# QEP.net
KiCad netlist of a schematic drawn in Altium Designer
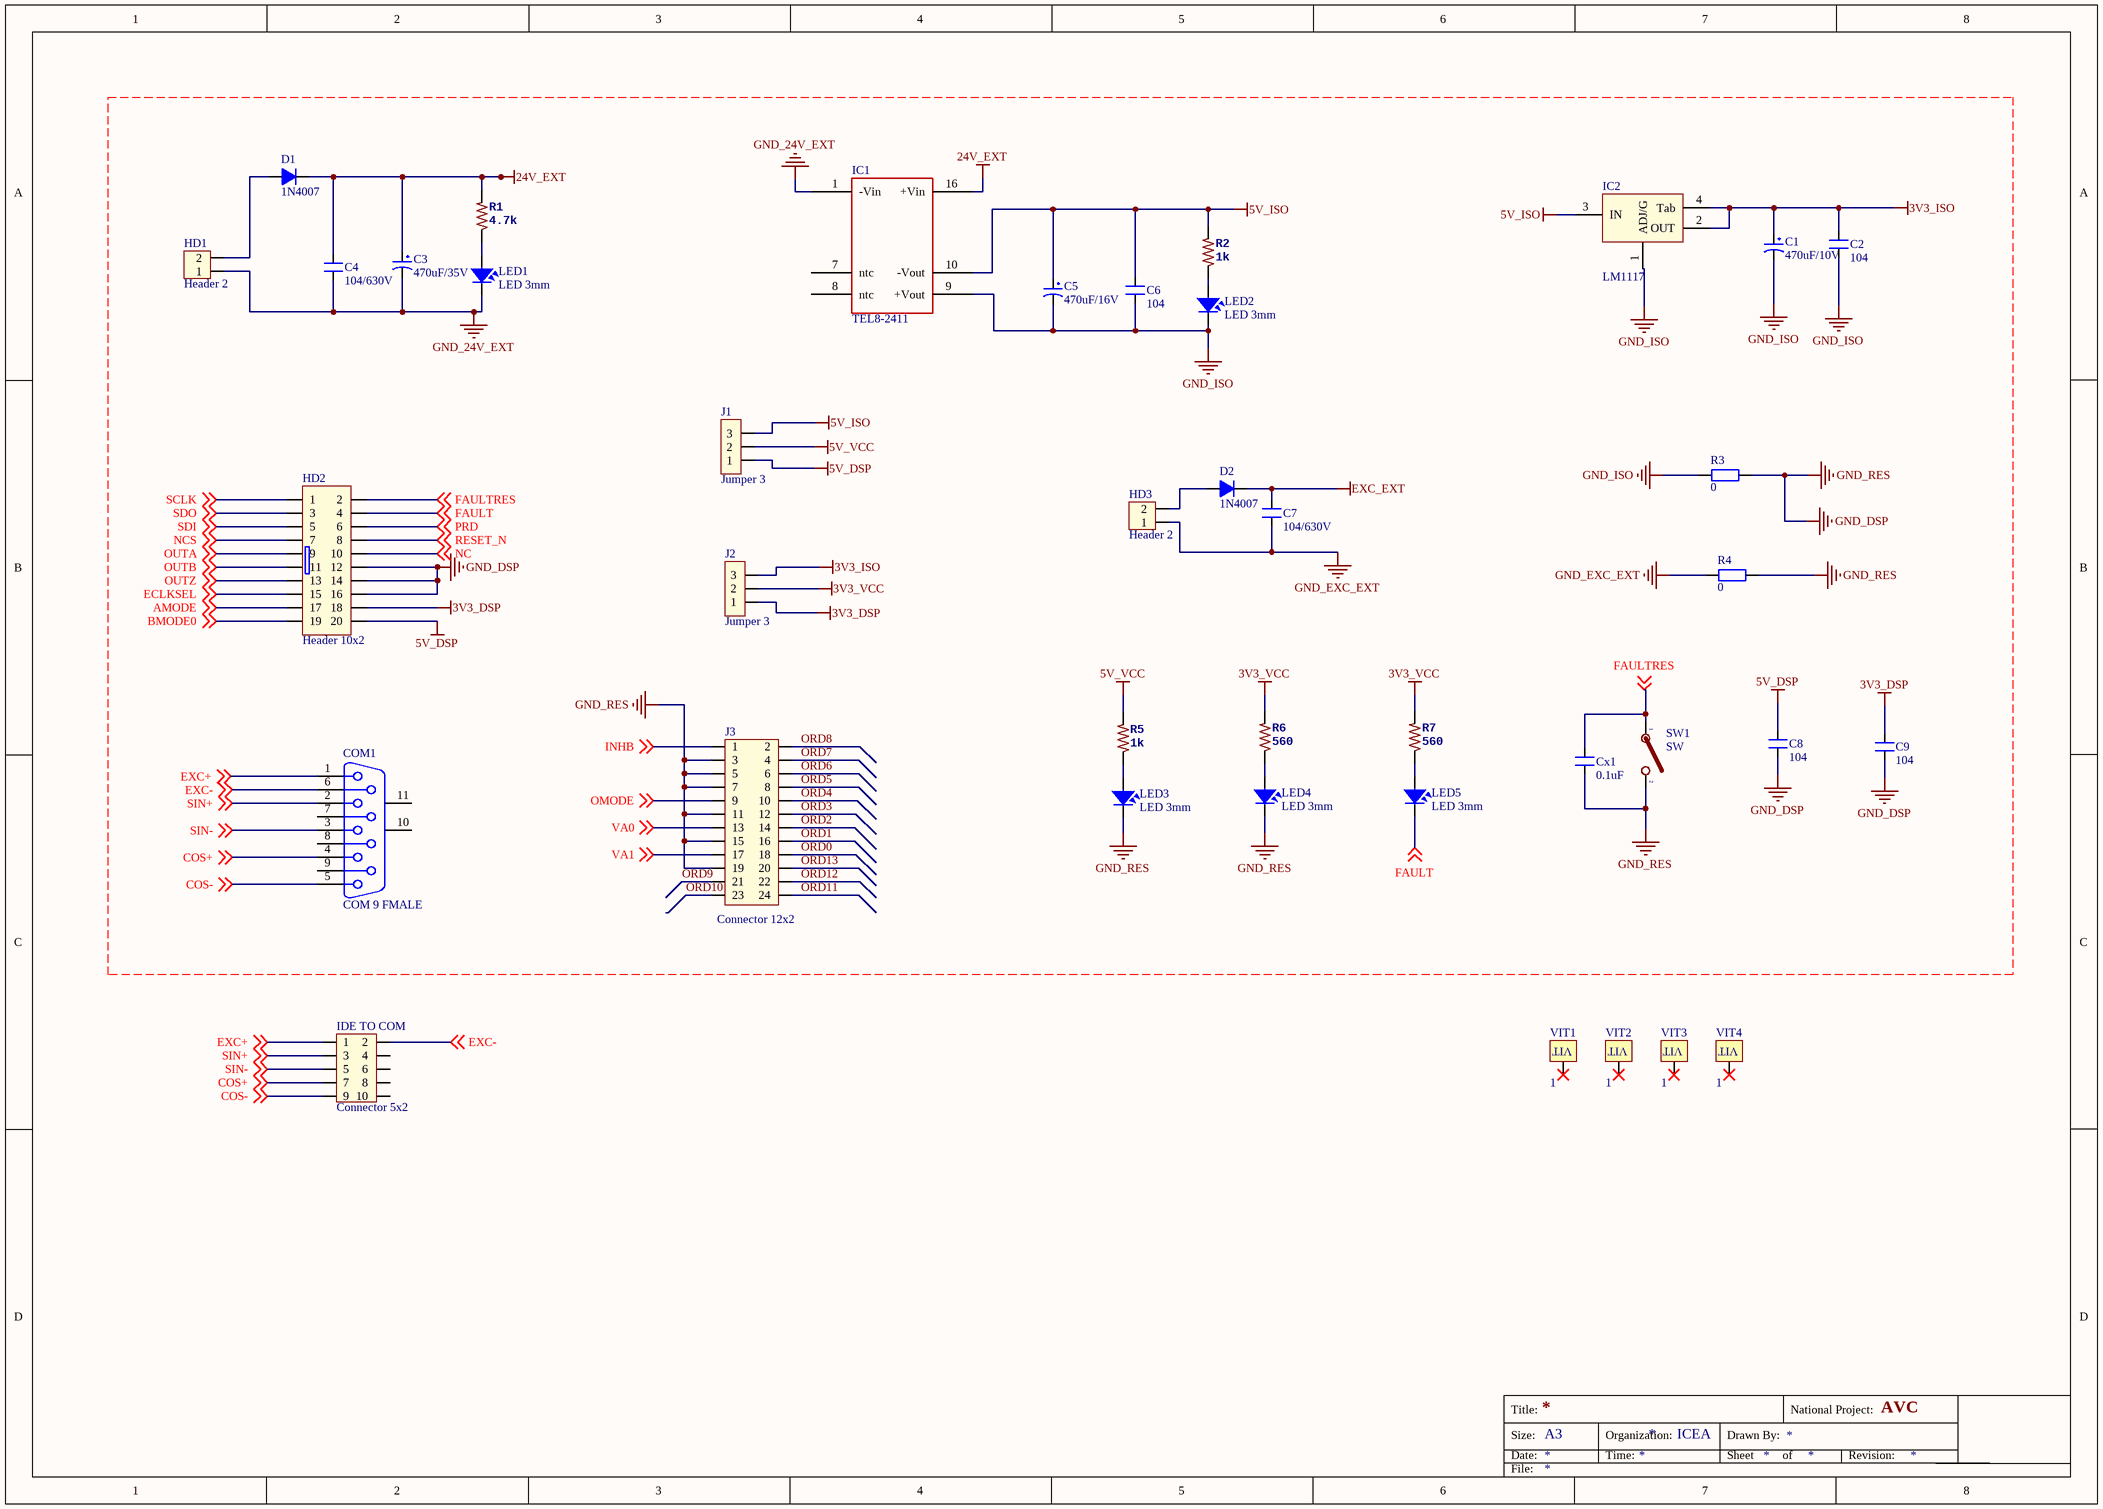
[diagram p0: QEP.SchDoc]

(export (version "E")
  (design (tool "Eeschema 10.0.6"))
  (components
    (comp (ref "C1")
      (value "470uF/10V")
      (footprint "CP 470uF/35V SMD 10x10mm")
      (description "Cap 100uF/35V - 470uF/16V")
      (libsource (lib "PELAB") (part "CP3"))
    )
    (comp (ref "C2")
      (value "104")
      (footprint "CN1.5")
      (description "Cap np 682pF => 104pF")
      (libsource (lib "PELAB") (part "CN1.5"))
    )
    (comp (ref "C3")
      (value "470uF/35V")
      (footprint "CP 470uF/35V SMD 10x10mm")
      (description "Cap 100uF/35V - 470uF/16V")
      (libsource (lib "PELAB") (part "CP3"))
    )
    (comp (ref "C4")
      (value "104/630V")
      (footprint "CN3")
      (description "Cap np W0.3")
      (fields (field (name "COPYRIGHT") "VanDungEvn"))
      (libsource (lib "PELAB") (part "CN3"))
    )
    (comp (ref "C5")
      (value "470uF/16V")
      (footprint "CP 470uF/35V SMD 10x10mm")
      (description "Cap 100uF/35V - 470uF/16V")
      (libsource (lib "PELAB") (part "CP3"))
    )
    (comp (ref "C6")
      (value "104")
      (footprint "CN1.5")
      (description "Cap np 682pF => 104pF")
      (libsource (lib "PELAB") (part "CN1.5"))
    )
    (comp (ref "C7")
      (value "104/630V")
      (footprint "CN3")
      (description "Cap np W0.3")
      (fields (field (name "COPYRIGHT") "VanDungEvn"))
      (libsource (lib "PELAB") (part "CN3"))
    )
    (comp (ref "C8")
      (value "104")
      (footprint "CN1.5")
      (description "Cap np 682pF => 104pF")
      (libsource (lib "PELAB") (part "CN1.5"))
    )
    (comp (ref "C9")
      (value "104")
      (footprint "CN1.5")
      (description "Cap np 682pF => 104pF")
      (libsource (lib "PELAB") (part "CN1.5"))
    )
    (comp (ref "COM1")
      (value "COM 9 FMALE")
      (footprint "DSB 9-F")
      (description "COM 9")
      (fields (field (name "PUBLISHER") "Altium Limited"))
      (libsource (lib "PELAB") (part "DSB9F"))
    )
    (comp (ref "Cx1")
      (value "0.1uF")
      (footprint "CN-SMD-0805")
      (libsource (lib "ImetAltiumLibrary") (part "CN"))
    )
    (comp (ref "D1")
      (value "1N4007")
      (footprint "DIO-SMD-106")
      (description "Diode 2A")
      (libsource (lib "PELAB") (part "D2A"))
    )
    (comp (ref "D2")
      (value "1N4007")
      (footprint "DIO-SMD-106")
      (description "Diode 2A")
      (libsource (lib "PELAB") (part "D2A"))
    )
    (comp (ref "HD1")
      (value "Header 2")
      (footprint "HED2T")
      (description "Header 2 (Green)")
      (libsource (lib "PELAB") (part "Hed2"))
    )
    (comp (ref "HD2") (value "Header 10x2") (footprint "IDE 20") (libsource (lib "PELAB") (part "HED10X2")))
    (comp (ref "HD3")
      (value "Header 2")
      (footprint "HED2T")
      (description "Header 2 (Green)")
      (libsource (lib "PELAB") (part "Hed2"))
    )
    (comp (ref "IC1")
      (value "TEL8-2411")
      (footprint "TEL8-2411")
      (libsource (lib "PELAB") (part "TEL8-2411"))
    )
    (comp (ref "IC2")
      (value "LM1117")
      (footprint "SOT223-4N")
      (description "3v3")
      (libsource (lib "PELAB") (part "LM1117"))
    )
    (comp (ref "IDE TO COM")
      (value "Connector 5x2")
      (footprint "IDE 10 duc")
      (libsource (lib "PELAB") (part "JP5x2"))
    )
    (comp (ref "J1") (value "Jumper 3") (footprint "JP3-CLOSED") (libsource (lib "PELAB") (part "JP3")))
    (comp (ref "J2") (value "Jumper 3") (footprint "JP3-CLOSED") (libsource (lib "PELAB") (part "JP3")))
    (comp (ref "J3") (value "Connector 12x2") (footprint "JP12X2") (libsource (lib "PELAB") (part "JP12x2")))
    (comp (ref "LED1")
      (value "LED 3mm")
      (footprint "LED-0805-Red")
      (description "LED Single colour Green and Red")
      (libsource (lib "PELAB") (part "LED 3mm"))
    )
    (comp (ref "LED2")
      (value "LED 3mm")
      (footprint "LED-0805-Red")
      (description "LED Single colour Green and Red")
      (libsource (lib "PELAB") (part "LED 3mm"))
    )
    (comp (ref "LED3")
      (value "LED 3mm")
      (footprint "LED-0805-Red")
      (description "LED Single colour Green and Red")
      (libsource (lib "PELAB") (part "LED 3mm"))
    )
    (comp (ref "LED4")
      (value "LED 3mm")
      (footprint "LED-0805-Red")
      (description "LED Single colour Green and Red")
      (libsource (lib "PELAB") (part "LED 3mm"))
    )
    (comp (ref "LED5")
      (value "LED 3mm")
      (footprint "LED-0805-Red")
      (description "LED Single colour Green and Red")
      (libsource (lib "PELAB") (part "LED 3mm"))
    )
    (comp (ref "R1")
      (value "4.7k")
      (footprint "SM-0805")
      (description "RESISTOR, American symbol")
      (libsource (lib "PELAB") (part "R-US_R0805"))
    )
    (comp (ref "R2")
      (value "1k")
      (footprint "RES-SMD-0805")
      (description "RESISTOR, American symbol")
      (libsource (lib "PELAB") (part "R-US_R0805"))
    )
    (comp (ref "R3")
      (value "0")
      (footprint "RES-SMD-0805")
      (description "Resistor 1/4W")
      (libsource (lib "PELAB") (part "R1/4W"))
    )
    (comp (ref "R4")
      (value "0")
      (footprint "RES-SMD-0805")
      (description "Resistor 1/4W")
      (libsource (lib "PELAB") (part "R1/4W"))
    )
    (comp (ref "R5")
      (value "1k")
      (footprint "RES-SMD-0805")
      (description "RESISTOR, American symbol")
      (libsource (lib "PELAB") (part "R-US_R0805"))
    )
    (comp (ref "R6")
      (value "560")
      (footprint "RES-SMD-0805")
      (description "RESISTOR, American symbol")
      (libsource (lib "PELAB") (part "R-US_R0805"))
    )
    (comp (ref "R7")
      (value "560")
      (footprint "RES-SMD-0805")
      (description "RESISTOR, American symbol")
      (libsource (lib "PELAB") (part "R-US_R0805"))
    )
    (comp (ref "SW1")
      (value "SW")
      (footprint "SW-SMD")
      (description "Switch button 2 pin")
      (libsource (lib "PELAB") (part "SW"))
    )
    (comp (ref "VIT1")
      (value "1")
      (footprint "VIT")
      (description "Oc Vit")
      (libsource (lib "PELAB") (part "VIT"))
    )
    (comp (ref "VIT2")
      (value "1")
      (footprint "VIT")
      (description "Oc Vit")
      (libsource (lib "PELAB") (part "VIT"))
    )
    (comp (ref "VIT3")
      (value "1")
      (footprint "VIT")
      (description "Oc Vit")
      (libsource (lib "PELAB") (part "VIT"))
    )
    (comp (ref "VIT4")
      (value "1")
      (footprint "VIT")
      (description "Oc Vit")
      (libsource (lib "PELAB") (part "VIT"))
    )
  )
  (nets
    (net (code "1") (name "/ORD0") (class "Default")
      (node (ref "J3") (pin "18") (pinfunction "18_18") (pintype "passive"))
    )
    (net (code "2") (name "/ORD1") (class "Default")
      (node (ref "J3") (pin "16") (pinfunction "16_16") (pintype "passive"))
    )
    (net (code "3") (name "/ORD2") (class "Default")
      (node (ref "J3") (pin "14") (pinfunction "14_14") (pintype "passive"))
    )
    (net (code "4") (name "/ORD3") (class "Default")
      (node (ref "J3") (pin "12") (pinfunction "12_12") (pintype "passive"))
    )
    (net (code "5") (name "/ORD4") (class "Default")
      (node (ref "J3") (pin "10") (pinfunction "10_10") (pintype "passive"))
    )
    (net (code "6") (name "/ORD5") (class "Default")
      (node (ref "J3") (pin "8") (pinfunction "8_8") (pintype "passive"))
    )
    (net (code "7") (name "/ORD6") (class "Default")
      (node (ref "J3") (pin "6") (pinfunction "6_6") (pintype "passive"))
    )
    (net (code "8") (name "/ORD7") (class "Default")
      (node (ref "J3") (pin "4") (pinfunction "4_4") (pintype "passive"))
    )
    (net (code "9") (name "/ORD8") (class "Default")
      (node (ref "J3") (pin "2") (pinfunction "2_2") (pintype "passive"))
    )
    (net (code "10") (name "/ORD9") (class "Default")
      (node (ref "J3") (pin "21") (pinfunction "21_21") (pintype "passive"))
    )
    (net (code "11") (name "/ORD10") (class "Default")
      (node (ref "J3") (pin "23") (pinfunction "23_23") (pintype "passive"))
    )
    (net (code "12") (name "/ORD11") (class "Default")
      (node (ref "J3") (pin "24") (pinfunction "24_24") (pintype "passive"))
    )
    (net (code "13") (name "/ORD12") (class "Default")
      (node (ref "J3") (pin "22") (pinfunction "22_22") (pintype "passive"))
    )
    (net (code "14") (name "/ORD13") (class "Default")
      (node (ref "J3") (pin "20") (pinfunction "20_20") (pintype "passive"))
    )
    (net (code "15") (name "3V3_DSP") (class "Default")
      (node (ref "C9") (pin "2") (pinfunction "2_2") (pintype "passive"))
      (node (ref "HD2") (pin "18") (pinfunction "18_18") (pintype "passive"))
      (node (ref "J2") (pin "1") (pinfunction "1_1") (pintype "passive"))
    )
    (net (code "16") (name "3V3_ISO") (class "Default")
      (node (ref "C1") (pin "1") (pinfunction "1_1") (pintype "passive"))
      (node (ref "C2") (pin "2") (pinfunction "2_2") (pintype "passive"))
      (node (ref "IC2") (pin "2") (pinfunction "OUT_2") (pintype "passive"))
      (node (ref "IC2") (pin "4") (pinfunction "Tab_4") (pintype "passive"))
      (node (ref "J2") (pin "3") (pinfunction "3_3") (pintype "passive"))
    )
    (net (code "17") (name "3V3_VCC") (class "Default")
      (node (ref "J2") (pin "2") (pinfunction "2_2") (pintype "passive"))
      (node (ref "R6") (pin "2") (pinfunction "2_2") (pintype "passive"))
      (node (ref "R7") (pin "2") (pinfunction "2_2") (pintype "passive"))
    )
    (net (code "18") (name "5V_DSP") (class "Default")
      (node (ref "C8") (pin "2") (pinfunction "2_2") (pintype "passive"))
      (node (ref "HD2") (pin "20") (pinfunction "20_20") (pintype "passive"))
      (node (ref "J1") (pin "1") (pinfunction "1_1") (pintype "passive"))
    )
    (net (code "19") (name "5V_ISO") (class "Default")
      (node (ref "C5") (pin "1") (pinfunction "1_1") (pintype "passive"))
      (node (ref "C6") (pin "2") (pinfunction "2_2") (pintype "passive"))
      (node (ref "IC1") (pin "10") (pinfunction "-Vout_10") (pintype "passive"))
      (node (ref "IC2") (pin "3") (pinfunction "IN_3") (pintype "passive"))
      (node (ref "J1") (pin "3") (pinfunction "3_3") (pintype "passive"))
      (node (ref "R2") (pin "2") (pinfunction "2_2") (pintype "passive"))
    )
    (net (code "20") (name "5V_VCC") (class "Default")
      (node (ref "J1") (pin "2") (pinfunction "2_2") (pintype "passive"))
      (node (ref "R5") (pin "2") (pinfunction "2_2") (pintype "passive"))
    )
    (net (code "21") (name "24V_EXT") (class "Default")
      (node (ref "C3") (pin "1") (pinfunction "1_1") (pintype "passive"))
      (node (ref "C4") (pin "2") (pinfunction "2_2") (pintype "passive"))
      (node (ref "D1") (pin "2") (pinfunction "K_2") (pintype "passive"))
      (node (ref "IC1") (pin "16") (pinfunction "+Vin_16") (pintype "passive"))
      (node (ref "R1") (pin "2") (pinfunction "2_2") (pintype "passive"))
    )
    (net (code "22") (name "AMODE") (class "Default")
      (node (ref "HD2") (pin "17") (pinfunction "17_17") (pintype "passive"))
    )
    (net (code "23") (name "BMODE0") (class "Default")
      (node (ref "HD2") (pin "19") (pinfunction "19_19") (pintype "passive"))
    )
    (net (code "24") (name "COS+") (class "Default")
      (node (ref "COM1") (pin "4") (pinfunction "4_4") (pintype "passive"))
      (node (ref "IDE TO COM") (pin "7") (pinfunction "7_7") (pintype "passive"))
    )
    (net (code "25") (name "COS-") (class "Default")
      (node (ref "COM1") (pin "5") (pinfunction "5_5") (pintype "passive"))
      (node (ref "IDE TO COM") (pin "9") (pinfunction "9_9") (pintype "passive"))
    )
    (net (code "26") (name "ECLKSEL") (class "Default")
      (node (ref "HD2") (pin "15") (pinfunction "15_15") (pintype "passive"))
    )
    (net (code "27") (name "EXC+") (class "Default")
      (node (ref "COM1") (pin "1") (pinfunction "1_1") (pintype "passive"))
      (node (ref "IDE TO COM") (pin "1") (pinfunction "1_1") (pintype "passive"))
    )
    (net (code "28") (name "EXC-") (class "Default")
      (node (ref "COM1") (pin "6") (pinfunction "6_6") (pintype "passive"))
      (node (ref "IDE TO COM") (pin "2") (pinfunction "2_2") (pintype "passive"))
    )
    (net (code "29") (name "EXC_EXT") (class "Default")
      (node (ref "C7") (pin "2") (pinfunction "2_2") (pintype "passive"))
      (node (ref "D2") (pin "2") (pinfunction "K_2") (pintype "passive"))
    )
    (net (code "30") (name "FAULT") (class "Default")
      (node (ref "HD2") (pin "4") (pinfunction "4_4") (pintype "passive"))
      (node (ref "LED5") (pin "2") (pinfunction "2_2") (pintype "passive"))
    )
    (net (code "31") (name "FAULTRES") (class "Default")
      (node (ref "Cx1") (pin "2") (pinfunction "2_2") (pintype "passive"))
      (node (ref "HD2") (pin "2") (pinfunction "2_2") (pintype "passive"))
      (node (ref "SW1") (pin "1") (pinfunction "1_1") (pintype "passive"))
    )
    (net (code "32") (name "GND_24V_EXT") (class "Default")
      (node (ref "C3") (pin "2") (pinfunction "2_2") (pintype "passive"))
      (node (ref "C4") (pin "1") (pinfunction "1_1") (pintype "passive"))
      (node (ref "HD1") (pin "1") (pinfunction "1_1") (pintype "passive"))
      (node (ref "IC1") (pin "1") (pinfunction "-Vin_1") (pintype "passive"))
      (node (ref "LED1") (pin "2") (pinfunction "2_2") (pintype "passive"))
    )
    (net (code "33") (name "GND_DSP") (class "Default")
      (node (ref "C8") (pin "1") (pinfunction "1_1") (pintype "passive"))
      (node (ref "C9") (pin "1") (pinfunction "1_1") (pintype "passive"))
      (node (ref "Cx1") (pin "1") (pinfunction "1_1") (pintype "passive"))
      (node (ref "HD2") (pin "12") (pinfunction "12_12") (pintype "passive"))
      (node (ref "HD2") (pin "14") (pinfunction "14_14") (pintype "passive"))
      (node (ref "HD2") (pin "16") (pinfunction "16_16") (pintype "passive"))
      (node (ref "J3") (pin "11") (pinfunction "11_11") (pintype "passive"))
      (node (ref "J3") (pin "15") (pinfunction "15_15") (pintype "passive"))
      (node (ref "J3") (pin "19") (pinfunction "19_19") (pintype "passive"))
      (node (ref "J3") (pin "3") (pinfunction "3_3") (pintype "passive"))
      (node (ref "J3") (pin "5") (pinfunction "5_5") (pintype "passive"))
      (node (ref "J3") (pin "7") (pinfunction "7_7") (pintype "passive"))
      (node (ref "LED3") (pin "2") (pinfunction "2_2") (pintype "passive"))
      (node (ref "LED4") (pin "2") (pinfunction "2_2") (pintype "passive"))
      (node (ref "R3") (pin "2") (pinfunction "2_2") (pintype "passive"))
      (node (ref "R4") (pin "2") (pinfunction "2_2") (pintype "passive"))
      (node (ref "SW1") (pin "2") (pinfunction "2_2") (pintype "passive"))
    )
    (net (code "34") (name "GND_EXC_EXT") (class "Default")
      (node (ref "C7") (pin "1") (pinfunction "1_1") (pintype "passive"))
      (node (ref "HD3") (pin "1") (pinfunction "1_1") (pintype "passive"))
      (node (ref "R4") (pin "1") (pinfunction "1_1") (pintype "passive"))
    )
    (net (code "35") (name "GND_ISO") (class "Default")
      (node (ref "C1") (pin "2") (pinfunction "2_2") (pintype "passive"))
      (node (ref "C2") (pin "1") (pinfunction "1_1") (pintype "passive"))
      (node (ref "C5") (pin "2") (pinfunction "2_2") (pintype "passive"))
      (node (ref "C6") (pin "1") (pinfunction "1_1") (pintype "passive"))
      (node (ref "IC1") (pin "9") (pinfunction "+Vout_9") (pintype "passive"))
      (node (ref "IC2") (pin "1") (pinfunction "ADJ/G_1") (pintype "passive"))
      (node (ref "LED2") (pin "2") (pinfunction "2_2") (pintype "passive"))
      (node (ref "R3") (pin "1") (pinfunction "1_1") (pintype "passive"))
    )
    (net (code "36") (name "INHB") (class "Default")
      (node (ref "J3") (pin "1") (pinfunction "1_1") (pintype "passive"))
    )
    (net (code "37") (name "NC") (class "Default")
      (node (ref "HD2") (pin "10") (pinfunction "10_10") (pintype "passive"))
    )
    (net (code "38") (name "NCS") (class "Default")
      (node (ref "HD2") (pin "7") (pinfunction "7_7") (pintype "passive"))
    )
    (net (code "39") (name "Net-(D1-A)") (class "Default")
      (node (ref "D1") (pin "1") (pinfunction "A_1") (pintype "passive"))
      (node (ref "HD1") (pin "2") (pinfunction "2_2") (pintype "passive"))
    )
    (net (code "40") (name "Net-(D2-A)") (class "Default")
      (node (ref "D2") (pin "1") (pinfunction "A_1") (pintype "passive"))
      (node (ref "HD3") (pin "2") (pinfunction "2_2") (pintype "passive"))
    )
    (net (code "41") (name "Net-(LED1-Pad1)") (class "Default")
      (node (ref "LED1") (pin "1") (pinfunction "1_1") (pintype "passive"))
      (node (ref "R1") (pin "1") (pinfunction "1_1") (pintype "passive"))
    )
    (net (code "42") (name "Net-(LED2-Pad1)") (class "Default")
      (node (ref "LED2") (pin "1") (pinfunction "1_1") (pintype "passive"))
      (node (ref "R2") (pin "1") (pinfunction "1_1") (pintype "passive"))
    )
    (net (code "43") (name "Net-(LED3-Pad1)") (class "Default")
      (node (ref "LED3") (pin "1") (pinfunction "1_1") (pintype "passive"))
      (node (ref "R5") (pin "1") (pinfunction "1_1") (pintype "passive"))
    )
    (net (code "44") (name "Net-(LED4-Pad1)") (class "Default")
      (node (ref "LED4") (pin "1") (pinfunction "1_1") (pintype "passive"))
      (node (ref "R6") (pin "1") (pinfunction "1_1") (pintype "passive"))
    )
    (net (code "45") (name "Net-(LED5-Pad1)") (class "Default")
      (node (ref "LED5") (pin "1") (pinfunction "1_1") (pintype "passive"))
      (node (ref "R7") (pin "1") (pinfunction "1_1") (pintype "passive"))
    )
    (net (code "46") (name "OMODE") (class "Default")
      (node (ref "J3") (pin "9") (pinfunction "9_9") (pintype "passive"))
    )
    (net (code "47") (name "OUTA") (class "Default")
      (node (ref "HD2") (pin "9") (pinfunction "9_9") (pintype "passive"))
    )
    (net (code "48") (name "OUTB") (class "Default")
      (node (ref "HD2") (pin "11") (pinfunction "11_11") (pintype "passive"))
    )
    (net (code "49") (name "OUTZ") (class "Default")
      (node (ref "HD2") (pin "13") (pinfunction "13_13") (pintype "passive"))
    )
    (net (code "50") (name "PRD") (class "Default")
      (node (ref "HD2") (pin "6") (pinfunction "6_6") (pintype "passive"))
    )
    (net (code "51") (name "RESET_N") (class "Default")
      (node (ref "HD2") (pin "8") (pinfunction "8_8") (pintype "passive"))
    )
    (net (code "52") (name "SCLK") (class "Default")
      (node (ref "HD2") (pin "1") (pinfunction "1_1") (pintype "passive"))
    )
    (net (code "53") (name "SDI") (class "Default")
      (node (ref "HD2") (pin "5") (pinfunction "5_5") (pintype "passive"))
    )
    (net (code "54") (name "SDO") (class "Default")
      (node (ref "HD2") (pin "3") (pinfunction "3_3") (pintype "passive"))
    )
    (net (code "55") (name "SIN+") (class "Default")
      (node (ref "COM1") (pin "2") (pinfunction "2_2") (pintype "passive"))
      (node (ref "IDE TO COM") (pin "3") (pinfunction "3_3") (pintype "passive"))
    )
    (net (code "56") (name "SIN-") (class "Default")
      (node (ref "COM1") (pin "3") (pinfunction "3_3") (pintype "passive"))
      (node (ref "IDE TO COM") (pin "5") (pinfunction "5_5") (pintype "passive"))
    )
    (net (code "57") (name "VA0") (class "Default")
      (node (ref "J3") (pin "13") (pinfunction "13_13") (pintype "passive"))
    )
    (net (code "58") (name "VA1") (class "Default")
      (node (ref "J3") (pin "17") (pinfunction "17_17") (pintype "passive"))
    )
    (net (code "59") (name "unconnected-(COM1-MH1-Pad10)") (class "Default")
      (node (ref "COM1") (pin "10") (pinfunction "MH1_10") (pintype "passive"))
    )
    (net (code "60") (name "unconnected-(COM1-MH2-Pad11)") (class "Default")
      (node (ref "COM1") (pin "11") (pinfunction "MH2_11") (pintype "passive"))
    )
    (net (code "61") (name "unconnected-(COM1-Pad7)") (class "Default")
      (node (ref "COM1") (pin "7") (pinfunction "7_7") (pintype "passive"))
    )
    (net (code "62") (name "unconnected-(COM1-Pad8)") (class "Default")
      (node (ref "COM1") (pin "8") (pinfunction "8_8") (pintype "passive"))
    )
    (net (code "63") (name "unconnected-(COM1-Pad9)") (class "Default")
      (node (ref "COM1") (pin "9") (pinfunction "9_9") (pintype "passive"))
    )
    (net (code "64") (name "unconnected-(IC1-ntc-Pad7)") (class "Default")
      (node (ref "IC1") (pin "7") (pinfunction "ntc_7") (pintype "passive"))
    )
    (net (code "65") (name "unconnected-(IC1-ntc-Pad8)") (class "Default")
      (node (ref "IC1") (pin "8") (pinfunction "ntc_8") (pintype "passive"))
    )
    (net (code "66") (name "unconnected-(IDE TO COM-Pad4)") (class "Default")
      (node (ref "IDE TO COM") (pin "4") (pinfunction "4_4") (pintype "passive"))
    )
    (net (code "67") (name "unconnected-(IDE TO COM-Pad6)") (class "Default")
      (node (ref "IDE TO COM") (pin "6") (pinfunction "6_6") (pintype "passive"))
    )
    (net (code "68") (name "unconnected-(IDE TO COM-Pad8)") (class "Default")
      (node (ref "IDE TO COM") (pin "8") (pinfunction "8_8") (pintype "passive"))
    )
    (net (code "69") (name "unconnected-(IDE TO COM-Pad10)") (class "Default")
      (node (ref "IDE TO COM") (pin "10") (pinfunction "10_10") (pintype "passive"))
    )
    (net (code "70") (name "unconnected-(VIT1-VIT-Pad1)") (class "Default")
      (node (ref "VIT1") (pin "1") (pinfunction "VIT_1") (pintype "passive+no_connect"))
    )
    (net (code "71") (name "unconnected-(VIT2-VIT-Pad1)") (class "Default")
      (node (ref "VIT2") (pin "1") (pinfunction "VIT_1") (pintype "passive+no_connect"))
    )
    (net (code "72") (name "unconnected-(VIT3-VIT-Pad1)") (class "Default")
      (node (ref "VIT3") (pin "1") (pinfunction "VIT_1") (pintype "passive+no_connect"))
    )
    (net (code "73") (name "unconnected-(VIT4-VIT-Pad1)") (class "Default")
      (node (ref "VIT4") (pin "1") (pinfunction "VIT_1") (pintype "passive+no_connect"))
    )
  )
)
